# mother_board_v2_0.net
KiCad netlist of a schematic drawn in EAGLE
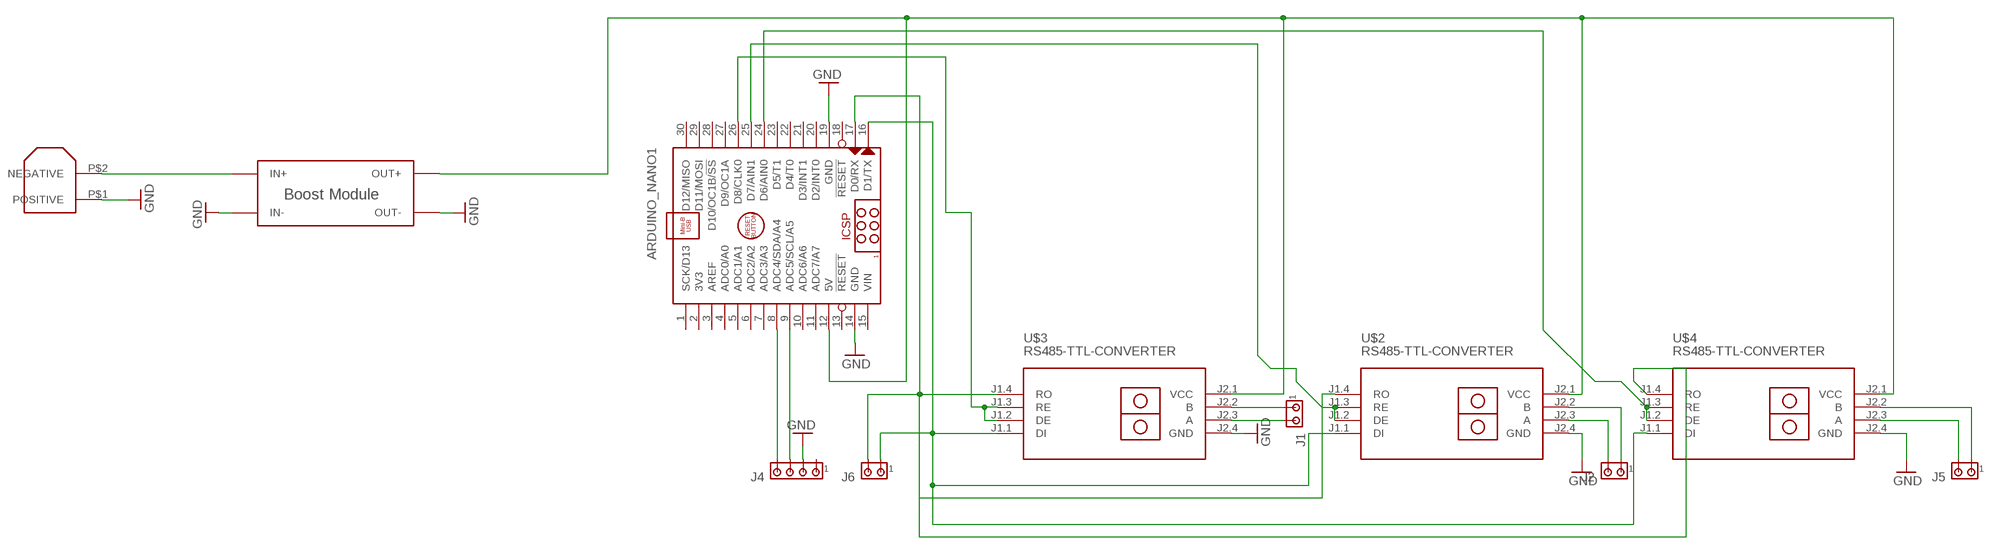
[diagram p0: schematic, sheet 1]

(export (version "E")
  (design (tool "Eeschema 10.0.6"))
  (components
    (comp (ref "ARDUINO_NANO1")
      (value "ARDUINO_NANO")
      (footprint "eagle-import:ARDUINO_NANO")
      (libsource (lib "eagle-import") (part "ARDUINO_NANO"))
    )
    (comp (ref "J1")
      (value "MTA02-100")
      (footprint "eagle-import:10X02MTA")
      (libsource (lib "eagle-import") (part "MTA02-100"))
    )
    (comp (ref "J2")
      (value "MTA02-100")
      (footprint "eagle-import:10X02MTA")
      (libsource (lib "eagle-import") (part "MTA02-100"))
    )
    (comp (ref "J4")
      (value "MTA04-100")
      (footprint "eagle-import:10X04MTA")
      (libsource (lib "eagle-import") (part "MTA04-100"))
    )
    (comp (ref "J5")
      (value "MTA02-100")
      (footprint "eagle-import:10X02MTA")
      (libsource (lib "eagle-import") (part "MTA02-100"))
    )
    (comp (ref "J6")
      (value "MTA02-100")
      (footprint "eagle-import:10X02MTA")
      (libsource (lib "eagle-import") (part "MTA02-100"))
    )
    (comp (ref "U$2")
      (value "RS485-TTL-CONVERTER")
      (footprint "eagle-import:RS485-TTL-CONVERTER")
      (libsource (lib "eagle-import") (part "RS485-TTL-CONVERTER"))
    )
    (comp (ref "U$3")
      (value "RS485-TTL-CONVERTER")
      (footprint "eagle-import:RS485-TTL-CONVERTER")
      (libsource (lib "eagle-import") (part "RS485-TTL-CONVERTER"))
    )
    (comp (ref "U$4")
      (value "RS485-TTL-CONVERTER")
      (footprint "eagle-import:RS485-TTL-CONVERTER")
      (libsource (lib "eagle-import") (part "RS485-TTL-CONVERTER"))
    )
    (comp (ref "U$5")
      (value "BOOST_MODULE")
      (footprint "eagle-import:BOOST_MODULE")
      (libsource (lib "eagle-import") (part "BOOST_MODULE"))
    )
    (comp (ref "U$6")
      (value "XT60")
      (footprint "eagle-import:CONNECTOR")
      (libsource (lib "eagle-import") (part "XT60"))
    )
  )
  (nets
    (net (code "1") (name "/VIN") (class "Default")
      (node (ref "ARDUINO_NANO1") (pin "15") (pinfunction "VIN_15") (pintype "power_in"))
    )
    (net (code "2") (name "GND") (class "Default")
      (node (ref "ARDUINO_NANO1") (pin "14") (pinfunction "GND_14") (pintype "power_in"))
      (node (ref "ARDUINO_NANO1") (pin "19") (pinfunction "GND_19") (pintype "power_in"))
      (node (ref "J4") (pin "2") (pinfunction "2_2") (pintype "passive"))
      (node (ref "U$2") (pin "J2.4") (pinfunction "GND_J2.4") (pintype "power_in"))
      (node (ref "U$3") (pin "J2.4") (pinfunction "GND_J2.4") (pintype "power_in"))
      (node (ref "U$4") (pin "J2.4") (pinfunction "GND_J2.4") (pintype "power_in"))
      (node (ref "U$5") (pin "IN-") (pinfunction "IN-_IN-") (pintype "bidirectional"))
      (node (ref "U$5") (pin "OUT-") (pinfunction "OUT-_OUT-") (pintype "bidirectional"))
      (node (ref "U$6") (pin "P$1") (pinfunction "POSITIVE_P$1") (pintype "bidirectional"))
    )
    (net (code "3") (name "Net-(ARDUINO_NANO1-5V)") (class "Default")
      (node (ref "ARDUINO_NANO1") (pin "12") (pinfunction "5V_12") (pintype "power_in"))
      (node (ref "U$2") (pin "J2.1") (pinfunction "VCC_J2.1") (pintype "power_in"))
      (node (ref "U$3") (pin "J2.1") (pinfunction "VCC_J2.1") (pintype "power_in"))
      (node (ref "U$4") (pin "J2.1") (pinfunction "VCC_J2.1") (pintype "power_in"))
      (node (ref "U$5") (pin "OUT+") (pinfunction "OUT+_OUT+") (pintype "bidirectional"))
    )
    (net (code "4") (name "Net-(ARDUINO_NANO1-ADC4{slash}SDA{slash}A4)") (class "Default")
      (node (ref "ARDUINO_NANO1") (pin "8") (pinfunction "ADC4/SDA/A4_8") (pintype "bidirectional"))
      (node (ref "J4") (pin "4") (pinfunction "4_4") (pintype "passive"))
    )
    (net (code "5") (name "Net-(ARDUINO_NANO1-ADC5{slash}SCL{slash}A5)") (class "Default")
      (node (ref "ARDUINO_NANO1") (pin "9") (pinfunction "ADC5/SCL/A5_9") (pintype "bidirectional"))
      (node (ref "J4") (pin "3") (pinfunction "3_3") (pintype "passive"))
    )
    (net (code "6") (name "Net-(ARDUINO_NANO1-D0{slash}RX)") (class "Default")
      (node (ref "ARDUINO_NANO1") (pin "17") (pinfunction "D0/RX_17") (pintype "bidirectional"))
      (node (ref "J6") (pin "2") (pinfunction "2_2") (pintype "passive"))
      (node (ref "U$2") (pin "J1.4") (pinfunction "RO_J1.4") (pintype "passive"))
      (node (ref "U$3") (pin "J1.4") (pinfunction "RO_J1.4") (pintype "passive"))
      (node (ref "U$4") (pin "J1.4") (pinfunction "RO_J1.4") (pintype "passive"))
    )
    (net (code "7") (name "Net-(ARDUINO_NANO1-D1{slash}TX)") (class "Default")
      (node (ref "ARDUINO_NANO1") (pin "16") (pinfunction "D1/TX_16") (pintype "bidirectional"))
      (node (ref "J6") (pin "1") (pinfunction "1_1") (pintype "passive"))
      (node (ref "U$2") (pin "J1.1") (pinfunction "DI_J1.1") (pintype "passive"))
      (node (ref "U$3") (pin "J1.1") (pinfunction "DI_J1.1") (pintype "passive"))
      (node (ref "U$4") (pin "J1.1") (pinfunction "DI_J1.1") (pintype "passive"))
    )
    (net (code "8") (name "Net-(ARDUINO_NANO1-D6{slash}AIN0)") (class "Default")
      (node (ref "ARDUINO_NANO1") (pin "24") (pinfunction "D6/AIN0_24") (pintype "bidirectional"))
      (node (ref "U$4") (pin "J1.2") (pinfunction "DE_J1.2") (pintype "passive"))
      (node (ref "U$4") (pin "J1.3") (pinfunction "RE_J1.3") (pintype "passive"))
    )
    (net (code "9") (name "Net-(ARDUINO_NANO1-D7{slash}AIN1)") (class "Default")
      (node (ref "ARDUINO_NANO1") (pin "25") (pinfunction "D7/AIN1_25") (pintype "bidirectional"))
      (node (ref "U$2") (pin "J1.2") (pinfunction "DE_J1.2") (pintype "passive"))
      (node (ref "U$2") (pin "J1.3") (pinfunction "RE_J1.3") (pintype "passive"))
    )
    (net (code "10") (name "Net-(ARDUINO_NANO1-D8{slash}CLK0)") (class "Default")
      (node (ref "ARDUINO_NANO1") (pin "26") (pinfunction "D8/CLK0_26") (pintype "bidirectional"))
      (node (ref "U$3") (pin "J1.2") (pinfunction "DE_J1.2") (pintype "passive"))
      (node (ref "U$3") (pin "J1.3") (pinfunction "RE_J1.3") (pintype "passive"))
    )
    (net (code "11") (name "Net-(U$2-A)") (class "Default")
      (node (ref "J2") (pin "2") (pinfunction "2_2") (pintype "passive"))
      (node (ref "U$2") (pin "J2.3") (pinfunction "A_J2.3") (pintype "passive"))
    )
    (net (code "12") (name "Net-(U$2-B)") (class "Default")
      (node (ref "J2") (pin "1") (pinfunction "1_1") (pintype "passive"))
      (node (ref "U$2") (pin "J2.2") (pinfunction "B_J2.2") (pintype "passive"))
    )
    (net (code "13") (name "Net-(U$3-A)") (class "Default")
      (node (ref "J1") (pin "2") (pinfunction "2_2") (pintype "passive"))
      (node (ref "U$3") (pin "J2.3") (pinfunction "A_J2.3") (pintype "passive"))
    )
    (net (code "14") (name "Net-(U$3-B)") (class "Default")
      (node (ref "J1") (pin "1") (pinfunction "1_1") (pintype "passive"))
      (node (ref "U$3") (pin "J2.2") (pinfunction "B_J2.2") (pintype "passive"))
    )
    (net (code "15") (name "Net-(U$4-A)") (class "Default")
      (node (ref "J5") (pin "2") (pinfunction "2_2") (pintype "passive"))
      (node (ref "U$4") (pin "J2.3") (pinfunction "A_J2.3") (pintype "passive"))
    )
    (net (code "16") (name "Net-(U$4-B)") (class "Default")
      (node (ref "J5") (pin "1") (pinfunction "1_1") (pintype "passive"))
      (node (ref "U$4") (pin "J2.2") (pinfunction "B_J2.2") (pintype "passive"))
    )
    (net (code "17") (name "Net-(U$6-NEGATIVE)") (class "Default")
      (node (ref "U$5") (pin "IN+") (pinfunction "IN+_IN+") (pintype "bidirectional"))
      (node (ref "U$6") (pin "P$2") (pinfunction "NEGATIVE_P$2") (pintype "bidirectional"))
    )
    (net (code "18") (name "unconnected-(ARDUINO_NANO1-3V3-Pad2)") (class "Default")
      (node (ref "ARDUINO_NANO1") (pin "2") (pinfunction "3V3_2") (pintype "output"))
    )
    (net (code "19") (name "unconnected-(ARDUINO_NANO1-ADC0{slash}A0-Pad4)") (class "Default")
      (node (ref "ARDUINO_NANO1") (pin "4") (pinfunction "ADC0/A0_4") (pintype "bidirectional"))
    )
    (net (code "20") (name "unconnected-(ARDUINO_NANO1-ADC1{slash}A1-Pad5)") (class "Default")
      (node (ref "ARDUINO_NANO1") (pin "5") (pinfunction "ADC1/A1_5") (pintype "bidirectional"))
    )
    (net (code "21") (name "unconnected-(ARDUINO_NANO1-ADC2{slash}A2-Pad6)") (class "Default")
      (node (ref "ARDUINO_NANO1") (pin "6") (pinfunction "ADC2/A2_6") (pintype "bidirectional"))
    )
    (net (code "22") (name "unconnected-(ARDUINO_NANO1-ADC3{slash}A3-Pad7)") (class "Default")
      (node (ref "ARDUINO_NANO1") (pin "7") (pinfunction "ADC3/A3_7") (pintype "bidirectional"))
    )
    (net (code "23") (name "unconnected-(ARDUINO_NANO1-ADC6{slash}A6-Pad10)") (class "Default")
      (node (ref "ARDUINO_NANO1") (pin "10") (pinfunction "ADC6/A6_10") (pintype "bidirectional"))
    )
    (net (code "24") (name "unconnected-(ARDUINO_NANO1-ADC7{slash}A7-Pad11)") (class "Default")
      (node (ref "ARDUINO_NANO1") (pin "11") (pinfunction "ADC7/A7_11") (pintype "bidirectional"))
    )
    (net (code "25") (name "unconnected-(ARDUINO_NANO1-AREF-Pad3)") (class "Default")
      (node (ref "ARDUINO_NANO1") (pin "3") (pinfunction "AREF_3") (pintype "input"))
    )
    (net (code "26") (name "unconnected-(ARDUINO_NANO1-D2{slash}INT0-Pad20)") (class "Default")
      (node (ref "ARDUINO_NANO1") (pin "20") (pinfunction "D2/INT0_20") (pintype "bidirectional"))
    )
    (net (code "27") (name "unconnected-(ARDUINO_NANO1-D3{slash}INT1-Pad21)") (class "Default")
      (node (ref "ARDUINO_NANO1") (pin "21") (pinfunction "D3/INT1_21") (pintype "bidirectional"))
    )
    (net (code "28") (name "unconnected-(ARDUINO_NANO1-D4{slash}T0-Pad22)") (class "Default")
      (node (ref "ARDUINO_NANO1") (pin "22") (pinfunction "D4/T0_22") (pintype "bidirectional"))
    )
    (net (code "29") (name "unconnected-(ARDUINO_NANO1-D5{slash}T1-Pad23)") (class "Default")
      (node (ref "ARDUINO_NANO1") (pin "23") (pinfunction "D5/T1_23") (pintype "bidirectional"))
    )
    (net (code "30") (name "unconnected-(ARDUINO_NANO1-D9{slash}OC1A-Pad27)") (class "Default")
      (node (ref "ARDUINO_NANO1") (pin "27") (pinfunction "D9/OC1A_27") (pintype "bidirectional"))
    )
    (net (code "31") (name "unconnected-(ARDUINO_NANO1-D10{slash}OC1B{slash}~{SS}-Pad28)") (class "Default")
      (node (ref "ARDUINO_NANO1") (pin "28") (pinfunction "D10/OC1B/~{SS}_28") (pintype "bidirectional"))
    )
    (net (code "32") (name "unconnected-(ARDUINO_NANO1-D11{slash}MOSI-Pad29)") (class "Default")
      (node (ref "ARDUINO_NANO1") (pin "29") (pinfunction "D11/MOSI_29") (pintype "bidirectional"))
    )
    (net (code "33") (name "unconnected-(ARDUINO_NANO1-D12{slash}MISO-Pad30)") (class "Default")
      (node (ref "ARDUINO_NANO1") (pin "30") (pinfunction "D12/MISO_30") (pintype "bidirectional"))
    )
    (net (code "34") (name "unconnected-(ARDUINO_NANO1-SCK{slash}D13-Pad1)") (class "Default")
      (node (ref "ARDUINO_NANO1") (pin "1") (pinfunction "SCK/D13_1") (pintype "bidirectional"))
    )
    (net (code "35") (name "unconnected-(ARDUINO_NANO1-~{RESET}-Pad13)") (class "Default")
      (node (ref "ARDUINO_NANO1") (pin "13") (pinfunction "~{RESET}_13") (pintype "input"))
    )
    (net (code "36") (name "unconnected-(ARDUINO_NANO1-~{RESET}-Pad18)") (class "Default")
      (node (ref "ARDUINO_NANO1") (pin "18") (pinfunction "~{RESET}_18") (pintype "input"))
    )
    (net (code "37") (name "unconnected-(J4-Pad1)") (class "Default")
      (node (ref "J4") (pin "1") (pinfunction "1_1") (pintype "passive"))
    )
  )
)
